# ESP32.net
KiCad netlist of a schematic drawn in Altium Designer
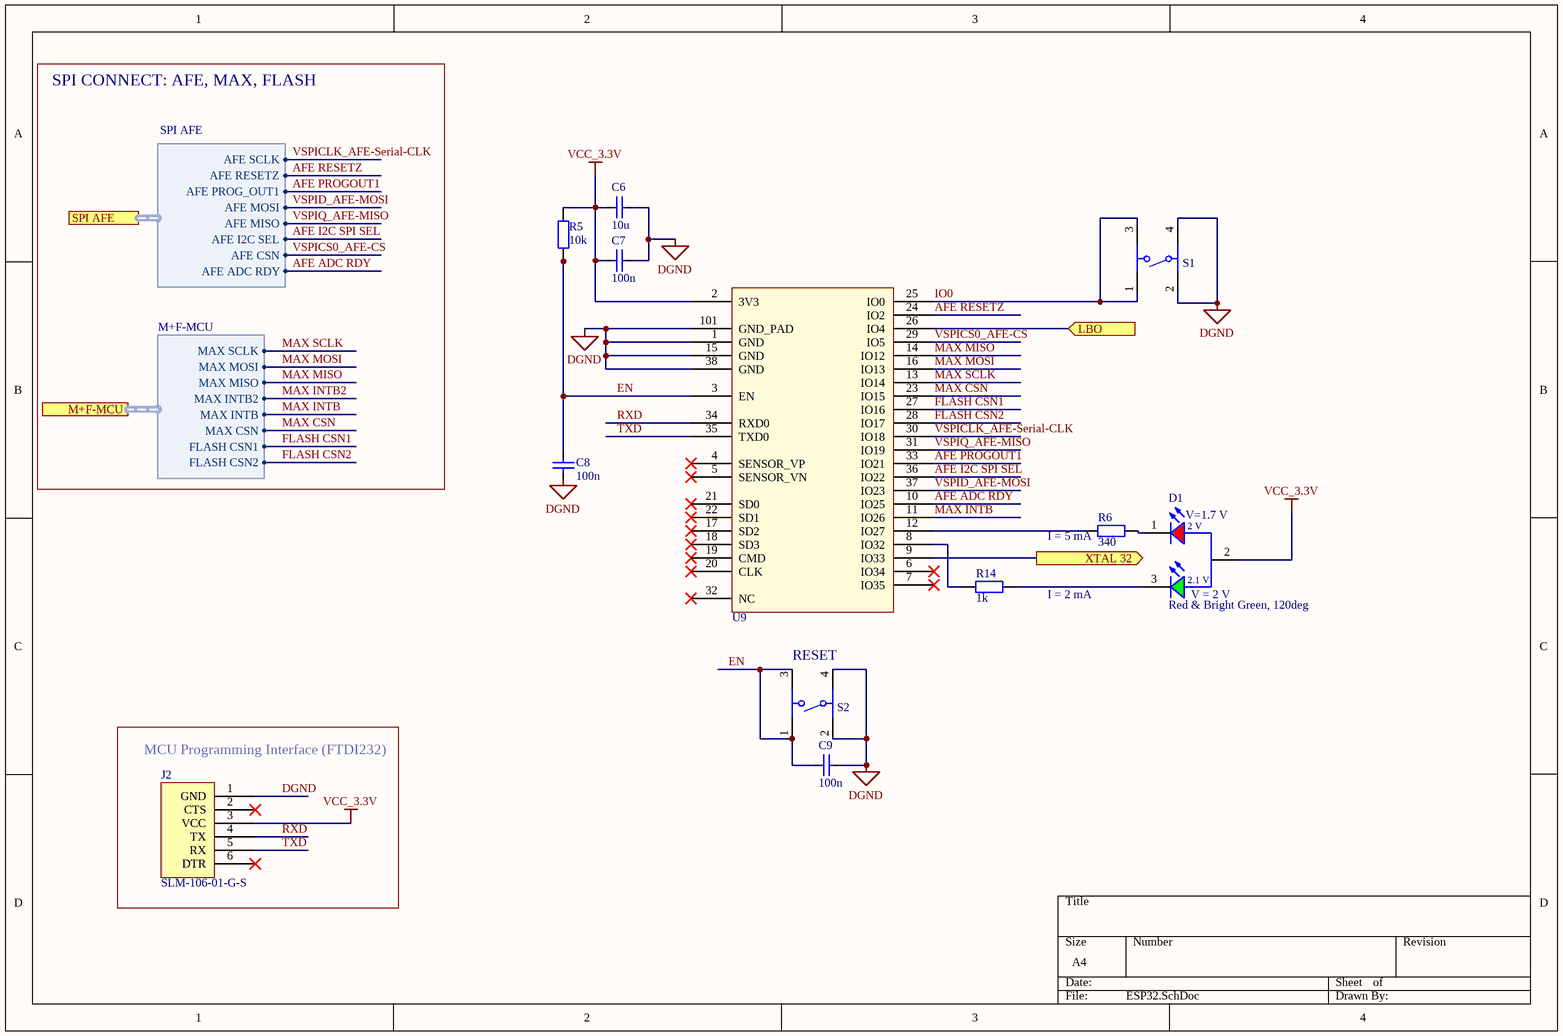
[diagram p0: ESP32.SchDoc]

(export (version "E")
  (design (tool "Eeschema 10.0.6"))
  (components
    (comp (ref "C6")
      (value "10u")
      (footprint "Lib_C:CAPC1608X05N")
      (description "Kondensator 10u 10V 0603")
      (libsource (lib "Lib_C") (part "C_10u_10V_0603"))
    )
    (comp (ref "C7")
      (value "100n")
      (footprint "Lib_C:CAPC1005X03N")
      (description "Kondensator 100n 50V 0402")
      (libsource (lib "Lib_C") (part "C_100n_50V_0402"))
    )
    (comp (ref "C8")
      (value "100n")
      (footprint "Lib_C:CAPC1005X03N")
      (description "Kondensator 100n 50V 0402")
      (libsource (lib "Lib_C") (part "C_100n_50V_0402"))
    )
    (comp (ref "C9")
      (value "100n")
      (footprint "Lib_C:CAPC1005X03N")
      (description "Kondensator 100n 50V 0402")
      (libsource (lib "Lib_C") (part "C_100n_50V_0402"))
    )
    (comp (ref "D1")
      (value "Red & Bright Green, 120deg")
      (footprint "WL-SBSW_1204")
      (description "WL-SBSW SMT Bi-color Side View Waterclear, size 1204, Red & Bright Green, 120deg")
      (fields (field (name "PART NUMBER") "155124RV73200") (field (name "PUBLISHER") "Wurth Elektronik"))
      (libsource (lib "Altium_WL-SBSW (rev19a)") (part "155124RV73200"))
    )
    (comp (ref "J2")
      (value "SLM-106-01-G-S")
      (footprint "SLM-106-01-G-S")
      (libsource (lib "Lib_Con") (part "SLM-106-01-G-S"))
    )
    (comp (ref "R5")
      (value "10k")
      (footprint "Lib_R:RESC1005X03N")
      (description "Widerstand 10k 1% 0402")
      (libsource (lib "Lib_R") (part "R_10k_0402"))
    )
    (comp (ref "R6")
      (value "340")
      (footprint "Lib_R:RESC1005X03N")
      (description "Widerstand 340R 0402")
      (libsource (lib "Lib_R") (part "R_0R_0402"))
    )
    (comp (ref "R14")
      (value "1k")
      (footprint "Lib_R:RESC1005X03N")
      (description "Widerstand 1k 1% 0402")
      (libsource (lib "Lib_R") (part "R_1k_0402"))
    )
    (comp (ref "S1")
      (value "434153017835")
      (footprint "434153017835")
      (description "3.5x2.9mm SMD J-Bend WS-TASV, height 1.7 mm, 350 gf")
      (fields (field (name "PUBLISHER") "Wurth Elektronik"))
      (libsource (lib "ALTIUM-WS-TASV-rev17b") (part "434153017835"))
    )
    (comp (ref "S2")
      (value "434153017835")
      (footprint "434153017835")
      (description "3.5x2.9mm SMD J-Bend WS-TASV, height 1.7 mm, 350 gf")
      (fields (field (name "PUBLISHER") "Wurth Elektronik"))
      (libsource (lib "ALTIUM-WS-TASV-rev17b") (part "434153017835"))
    )
    (comp (ref "U9")
      (value "ESP32")
      (footprint "ESP32-WROOM-32")
      (description "Espressiv ESP32-WROOM32 WLAN Bluetooth Module")
      (libsource (lib "Grosse_Microcontroller") (part "ESP32-WROOM32"))
    )
  )
  (nets
    (net (code "4") (name "/AFE ADC RDY") (class "Default")
      (node (ref "U9") (pin "10") (pinfunction "IO25_10") (pintype "passive"))
    )
    (net (code "5") (name "/AFE I2C SPI SEL") (class "Default")
      (node (ref "U9") (pin "36") (pinfunction "IO22_36") (pintype "passive"))
    )
    (net (code "6") (name "/AFE PROGOUT1") (class "Default")
      (node (ref "U9") (pin "33") (pinfunction "IO21_33") (pintype "passive"))
    )
    (net (code "7") (name "/AFE RESETZ") (class "Default")
      (node (ref "U9") (pin "24") (pinfunction "IO2_24") (pintype "passive"))
    )
    (net (code "8") (name "/EN") (class "Default")
      (node (ref "C8") (pin "2") (pinfunction "2_2") (pintype "passive"))
      (node (ref "C9") (pin "1") (pinfunction "1_1") (pintype "passive"))
      (node (ref "R5") (pin "1") (pinfunction "1_1") (pintype "passive"))
      (node (ref "S2") (pin "1") (pinfunction "1_1") (pintype "passive"))
      (node (ref "S2") (pin "3") (pinfunction "3_3") (pintype "passive"))
      (node (ref "U9") (pin "3") (pinfunction "EN_3") (pintype "power_in"))
    )
    (net (code "9") (name "/FLASH CSN1") (class "Default")
      (node (ref "U9") (pin "27") (pinfunction "IO16_27") (pintype "passive"))
    )
    (net (code "10") (name "/FLASH CSN2") (class "Default")
      (node (ref "U9") (pin "28") (pinfunction "IO17_28") (pintype "passive"))
    )
    (net (code "11") (name "/IO0") (class "Default")
      (node (ref "S1") (pin "1") (pinfunction "1_1") (pintype "passive"))
      (node (ref "S1") (pin "3") (pinfunction "3_3") (pintype "passive"))
      (node (ref "U9") (pin "25") (pinfunction "IO0_25") (pintype "passive"))
    )
    (net (code "12") (name "/LBO") (class "Default")
      (node (ref "U9") (pin "26") (pinfunction "IO4_26") (pintype "passive"))
    )
    (net (code "13") (name "/MAX CSN") (class "Default")
      (node (ref "U9") (pin "23") (pinfunction "IO15_23") (pintype "passive"))
    )
    (net (code "14") (name "/MAX INTB") (class "Default")
      (node (ref "U9") (pin "11") (pinfunction "IO26_11") (pintype "passive"))
    )
    (net (code "16") (name "/MAX MISO") (class "Default")
      (node (ref "U9") (pin "14") (pinfunction "IO12_14") (pintype "passive"))
    )
    (net (code "17") (name "/MAX MOSI") (class "Default")
      (node (ref "U9") (pin "16") (pinfunction "IO13_16") (pintype "passive"))
    )
    (net (code "18") (name "/MAX SCLK") (class "Default")
      (node (ref "U9") (pin "13") (pinfunction "IO14_13") (pintype "passive"))
    )
    (net (code "19") (name "/RXD") (class "Default")
      (node (ref "J2") (pin "4") (pinfunction "TX_4") (pintype "passive"))
      (node (ref "U9") (pin "34") (pinfunction "RXD0_34") (pintype "passive"))
    )
    (net (code "20") (name "/TXD") (class "Default")
      (node (ref "J2") (pin "5") (pinfunction "RX_5") (pintype "passive"))
      (node (ref "U9") (pin "35") (pinfunction "TXD0_35") (pintype "passive"))
    )
    (net (code "21") (name "/VSPICLK_AFE-Serial-CLK") (class "Default")
      (node (ref "U9") (pin "30") (pinfunction "IO18_30") (pintype "passive"))
    )
    (net (code "22") (name "/VSPICS0_AFE-CS") (class "Default")
      (node (ref "U9") (pin "29") (pinfunction "IO5_29") (pintype "passive"))
    )
    (net (code "23") (name "/VSPID_AFE-MOSI") (class "Default")
      (node (ref "U9") (pin "37") (pinfunction "IO23_37") (pintype "passive"))
    )
    (net (code "24") (name "/VSPIQ_AFE-MISO") (class "Default")
      (node (ref "U9") (pin "31") (pinfunction "IO19_31") (pintype "passive"))
    )
    (net (code "25") (name "/XTAL 32") (class "Default")
      (node (ref "U9") (pin "9") (pinfunction "IO33_9") (pintype "passive"))
    )
    (net (code "28") (name "DGND") (class "Default")
      (node (ref "C6") (pin "2") (pinfunction "2_2") (pintype "passive"))
      (node (ref "C7") (pin "2") (pinfunction "2_2") (pintype "passive"))
      (node (ref "C8") (pin "1") (pinfunction "1_1") (pintype "passive"))
      (node (ref "C9") (pin "2") (pinfunction "2_2") (pintype "passive"))
      (node (ref "J2") (pin "1") (pinfunction "GND_1") (pintype "passive"))
      (node (ref "S1") (pin "2") (pinfunction "2_2") (pintype "passive"))
      (node (ref "S1") (pin "4") (pinfunction "4_4") (pintype "passive"))
      (node (ref "S2") (pin "2") (pinfunction "2_2") (pintype "passive"))
      (node (ref "S2") (pin "4") (pinfunction "4_4") (pintype "passive"))
      (node (ref "U9") (pin "1") (pinfunction "GND_1") (pintype "power_in"))
      (node (ref "U9") (pin "101") (pinfunction "GND_PAD_101") (pintype "power_in"))
      (node (ref "U9") (pin "15") (pinfunction "GND_15") (pintype "power_in"))
      (node (ref "U9") (pin "38") (pinfunction "GND_38") (pintype "power_in"))
    )
    (net (code "29") (name "Net-(D1-K-Pad1)") (class "Default")
      (node (ref "D1") (pin "1") (pinfunction "K_1") (pintype "passive"))
      (node (ref "R6") (pin "2") (pinfunction "2_2") (pintype "passive"))
    )
    (net (code "30") (name "Net-(D1-K-Pad3)") (class "Default")
      (node (ref "D1") (pin "3") (pinfunction "K_3") (pintype "passive"))
      (node (ref "R14") (pin "2") (pinfunction "2_2") (pintype "passive"))
    )
    (net (code "31") (name "Net-(U9-IO27)") (class "Default")
      (node (ref "R6") (pin "1") (pinfunction "1_1") (pintype "passive"))
      (node (ref "U9") (pin "12") (pinfunction "IO27_12") (pintype "passive"))
    )
    (net (code "32") (name "Net-(U9-IO32)") (class "Default")
      (node (ref "R14") (pin "1") (pinfunction "1_1") (pintype "passive"))
      (node (ref "U9") (pin "8") (pinfunction "IO32_8") (pintype "passive"))
    )
    (net (code "33") (name "VCC_3.3V") (class "Default")
      (node (ref "C6") (pin "1") (pinfunction "1_1") (pintype "passive"))
      (node (ref "C7") (pin "1") (pinfunction "1_1") (pintype "passive"))
      (node (ref "D1") (pin "2") (pinfunction "A_2") (pintype "passive"))
      (node (ref "J2") (pin "3") (pinfunction "VCC_3") (pintype "passive"))
      (node (ref "R5") (pin "2") (pinfunction "2_2") (pintype "passive"))
      (node (ref "U9") (pin "2") (pinfunction "3V3_2") (pintype "power_in"))
    )
    (net (code "34") (name "unconnected-(J2-CTS-Pad2)") (class "Default")
      (node (ref "J2") (pin "2") (pinfunction "CTS_2") (pintype "passive+no_connect"))
    )
    (net (code "35") (name "unconnected-(J2-DTR-Pad6)") (class "Default")
      (node (ref "J2") (pin "6") (pinfunction "DTR_6") (pintype "passive+no_connect"))
    )
    (net (code "36") (name "unconnected-(U9-CLK-Pad20)") (class "Default")
      (node (ref "U9") (pin "20") (pinfunction "CLK_20") (pintype "passive+no_connect"))
    )
    (net (code "37") (name "unconnected-(U9-CMD-Pad19)") (class "Default")
      (node (ref "U9") (pin "19") (pinfunction "CMD_19") (pintype "passive+no_connect"))
    )
    (net (code "38") (name "unconnected-(U9-IO34-Pad6)") (class "Default")
      (node (ref "U9") (pin "6") (pinfunction "IO34_6") (pintype "passive+no_connect"))
    )
    (net (code "39") (name "unconnected-(U9-IO35-Pad7)") (class "Default")
      (node (ref "U9") (pin "7") (pinfunction "IO35_7") (pintype "passive+no_connect"))
    )
    (net (code "40") (name "unconnected-(U9-NC-Pad32)") (class "Default")
      (node (ref "U9") (pin "32") (pinfunction "NC_32") (pintype "passive+no_connect"))
    )
    (net (code "41") (name "unconnected-(U9-SD0-Pad21)") (class "Default")
      (node (ref "U9") (pin "21") (pinfunction "SD0_21") (pintype "passive+no_connect"))
    )
    (net (code "42") (name "unconnected-(U9-SD1-Pad22)") (class "Default")
      (node (ref "U9") (pin "22") (pinfunction "SD1_22") (pintype "passive+no_connect"))
    )
    (net (code "43") (name "unconnected-(U9-SD2-Pad17)") (class "Default")
      (node (ref "U9") (pin "17") (pinfunction "SD2_17") (pintype "passive+no_connect"))
    )
    (net (code "44") (name "unconnected-(U9-SD3-Pad18)") (class "Default")
      (node (ref "U9") (pin "18") (pinfunction "SD3_18") (pintype "passive+no_connect"))
    )
    (net (code "45") (name "unconnected-(U9-SENSOR_VN-Pad5)") (class "Default")
      (node (ref "U9") (pin "5") (pinfunction "SENSOR_VN_5") (pintype "passive+no_connect"))
    )
    (net (code "46") (name "unconnected-(U9-SENSOR_VP-Pad4)") (class "Default")
      (node (ref "U9") (pin "4") (pinfunction "SENSOR_VP_4") (pintype "passive+no_connect"))
    )
  )
)
